# usbcan_20190426.net
KiCad netlist of a schematic drawn in EAGLE
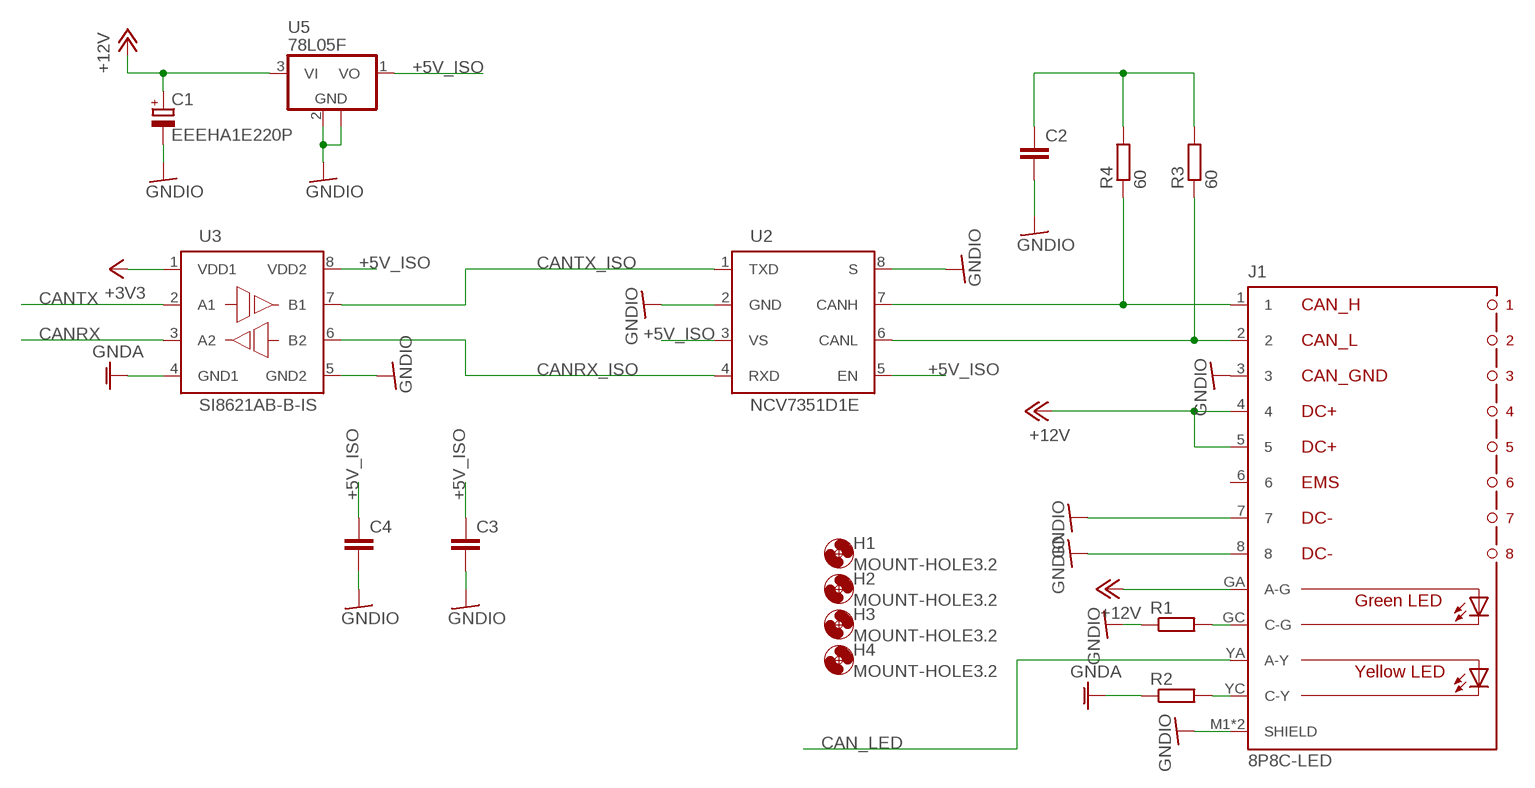
[diagram p0: schematic, sheet 1]
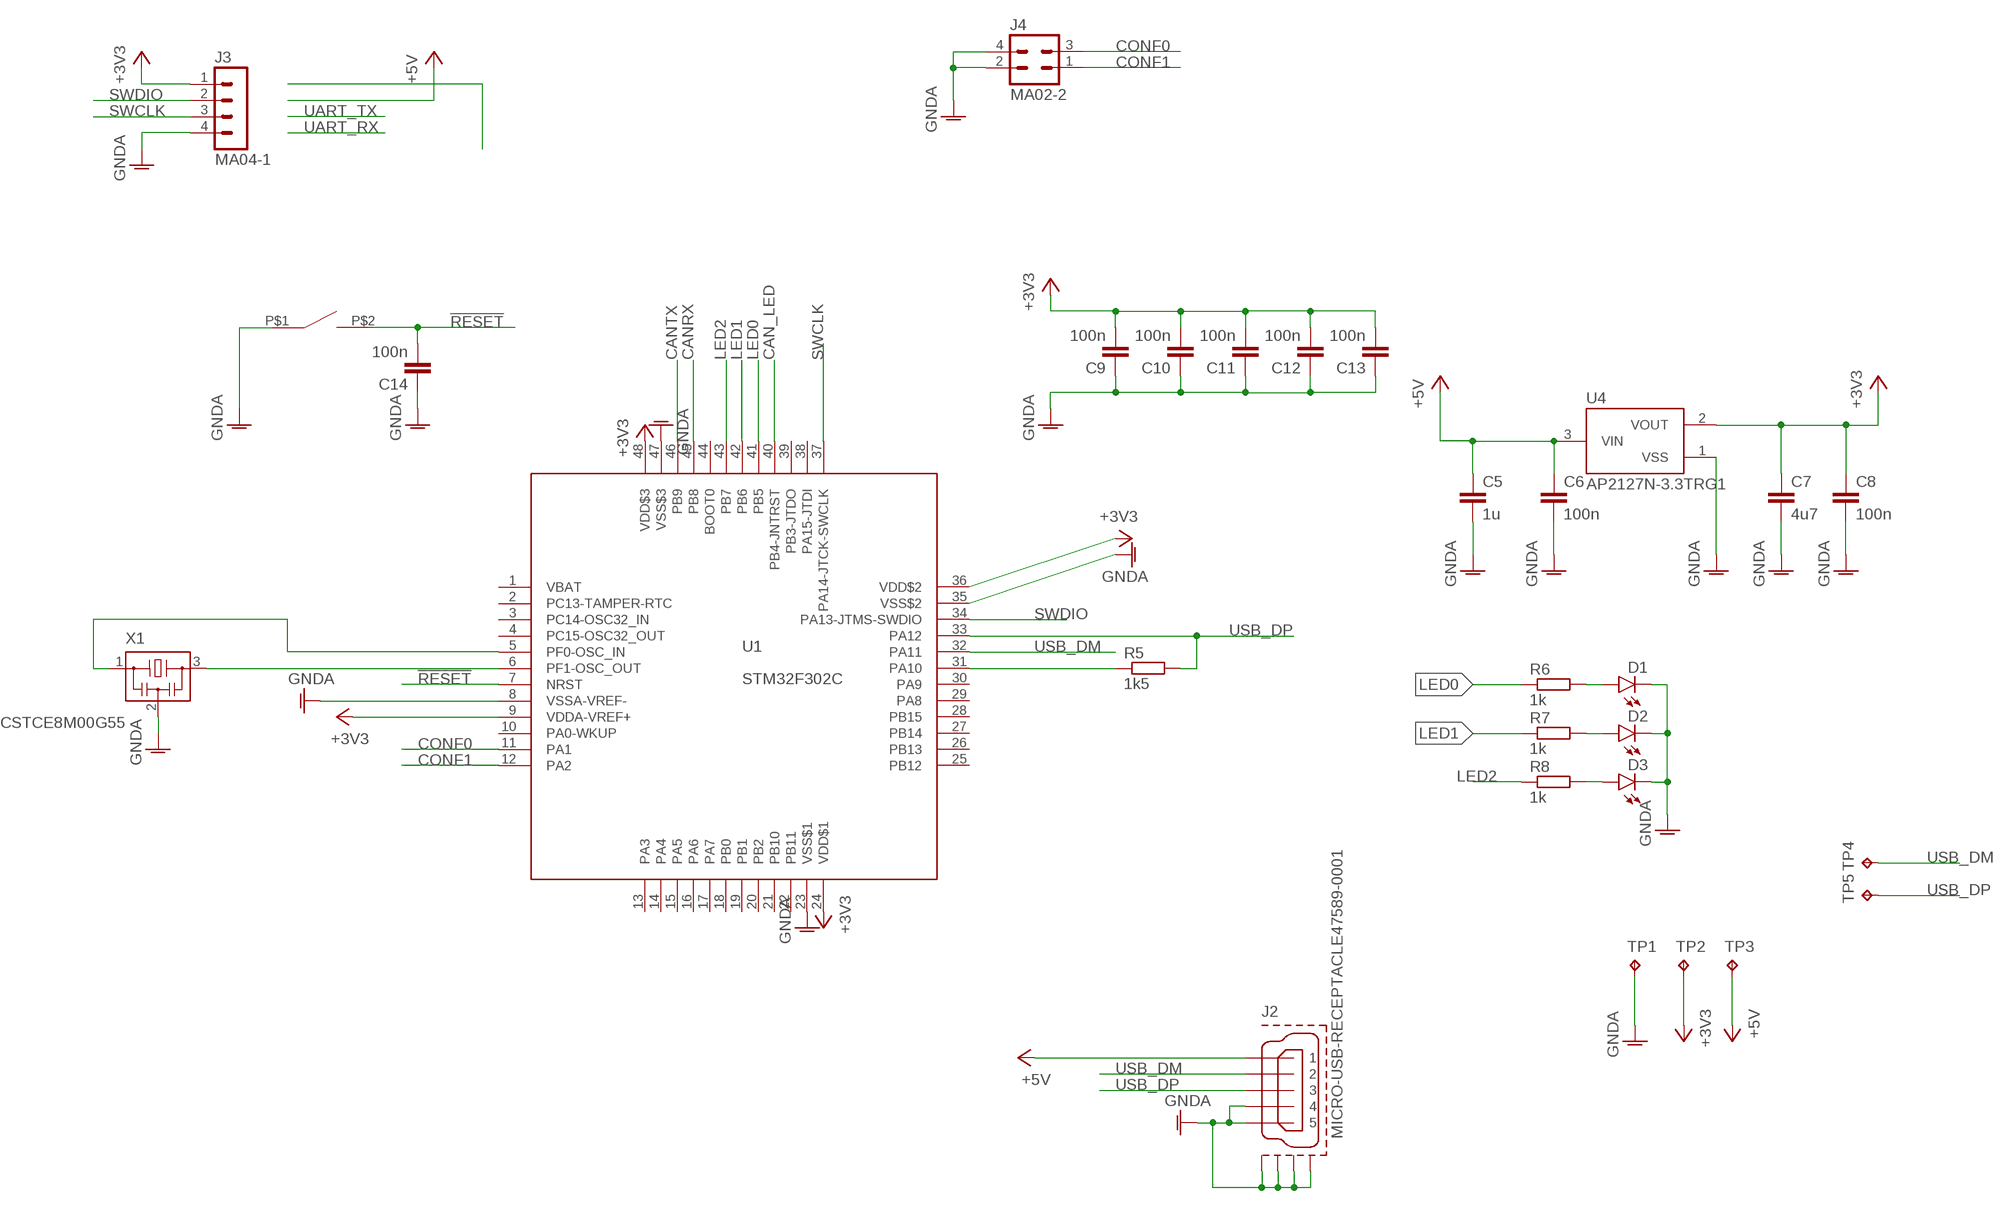
[diagram p1: schematic, sheet 2]

(export (version "E")
  (design (tool "Eeschema 10.0.6"))
  (components
    (comp (ref "C5")
      (value "1u")
      (footprint "eagle-import:C0603")
      (libsource (lib "eagle-import") (part "C-EUC0603"))
    )
    (comp (ref "C6")
      (value "100n")
      (footprint "eagle-import:C0603")
      (libsource (lib "eagle-import") (part "C-EUC0603"))
    )
    (comp (ref "C7")
      (value "4u7")
      (footprint "eagle-import:C0805")
      (libsource (lib "eagle-import") (part "C-EUC0805"))
    )
    (comp (ref "C8")
      (value "100n")
      (footprint "eagle-import:C0603")
      (libsource (lib "eagle-import") (part "C-EUC0603"))
    )
    (comp (ref "C9")
      (value "100n")
      (footprint "eagle-import:C0603")
      (libsource (lib "eagle-import") (part "C-EUC0603"))
    )
    (comp (ref "C10")
      (value "100n")
      (footprint "eagle-import:C0603")
      (libsource (lib "eagle-import") (part "C-EUC0603"))
    )
    (comp (ref "C11")
      (value "100n")
      (footprint "eagle-import:C0603")
      (libsource (lib "eagle-import") (part "C-EUC0603"))
    )
    (comp (ref "C12")
      (value "100n")
      (footprint "eagle-import:C0603")
      (libsource (lib "eagle-import") (part "C-EUC0603"))
    )
    (comp (ref "C13")
      (value "100n")
      (footprint "eagle-import:C0603")
      (libsource (lib "eagle-import") (part "C-EUC0603"))
    )
    (comp (ref "C14")
      (value "100n")
      (footprint "eagle-import:C0603")
      (libsource (lib "eagle-import") (part "C-EUC0603"))
    )
    (comp (ref "D1")
      (value "LEDCHIPLED_0805")
      (footprint "eagle-import:CHIPLED_0805")
      (libsource (lib "eagle-import") (part "LEDCHIPLED_0805"))
    )
    (comp (ref "D2")
      (value "LEDCHIPLED_0805")
      (footprint "eagle-import:CHIPLED_0805")
      (libsource (lib "eagle-import") (part "LEDCHIPLED_0805"))
    )
    (comp (ref "D3")
      (value "LEDCHIPLED_0805")
      (footprint "eagle-import:CHIPLED_0805")
      (libsource (lib "eagle-import") (part "LEDCHIPLED_0805"))
    )
    (comp (ref "J2")
      (value "MICRO-USB-RECEPTACLE47589-0001")
      (footprint "eagle-import:47589-0001")
      (libsource (lib "eagle-import") (part "MICRO-USB-RECEPTACLE47589-0001"))
    )
    (comp (ref "J3")
      (value "MA04-1")
      (footprint "eagle-import:MA04-1")
      (libsource (lib "eagle-import") (part "MA04-1"))
    )
    (comp (ref "J4")
      (value "MA02-2")
      (footprint "eagle-import:MA02-2W")
      (libsource (lib "eagle-import") (part "MA02-2"))
    )
    (comp (ref "R5")
      (value "1k5")
      (footprint "eagle-import:R0603")
      (libsource (lib "eagle-import") (part "R-EU_R0603"))
    )
    (comp (ref "R6")
      (value "1k")
      (footprint "eagle-import:R0603")
      (libsource (lib "eagle-import") (part "R-EU_R0603"))
    )
    (comp (ref "R7")
      (value "1k")
      (footprint "eagle-import:R0603")
      (libsource (lib "eagle-import") (part "R-EU_R0603"))
    )
    (comp (ref "R8")
      (value "1k")
      (footprint "eagle-import:R0603")
      (libsource (lib "eagle-import") (part "R-EU_R0603"))
    )
    (comp (ref "S1")
      (value "SWITCH_TACTILETOP")
      (footprint "eagle-import:SWITCH_TACTILE_3X6")
      (libsource (lib "eagle-import") (part "SWITCH_TACTILETOP"))
    )
    (comp (ref "TP1")
      (value "TPB1,27")
      (footprint "eagle-import:B1,27")
      (libsource (lib "eagle-import") (part "TPB1,27"))
    )
    (comp (ref "TP2")
      (value "TPB1,27")
      (footprint "eagle-import:B1,27")
      (libsource (lib "eagle-import") (part "TPB1,27"))
    )
    (comp (ref "TP3")
      (value "TPB1,27")
      (footprint "eagle-import:B1,27")
      (libsource (lib "eagle-import") (part "TPB1,27"))
    )
    (comp (ref "TP4")
      (value "TPB1,27")
      (footprint "eagle-import:B1,27")
      (libsource (lib "eagle-import") (part "TPB1,27"))
    )
    (comp (ref "TP5")
      (value "TPB1,27")
      (footprint "eagle-import:B1,27")
      (libsource (lib "eagle-import") (part "TPB1,27"))
    )
    (comp (ref "U1")
      (value "STM32F302C")
      (footprint "eagle-import:LQFP48")
      (libsource (lib "eagle-import") (part "STM32F303C"))
    )
    (comp (ref "U4")
      (value "AP2127N-3.3TRG1")
      (footprint "eagle-import:SOT95P240X110-3")
      (libsource (lib "eagle-import") (part "XC6206"))
    )
    (comp (ref "X1")
      (value "CSTCE8M00G55")
      (footprint "eagle-import:CSTCE8M00G55")
      (libsource (lib "eagle-import") (part "CSTCE8M00G55"))
    )
    (comp (ref "C1")
      (value "EEEHA1E220P")
      (footprint "eagle-import:153CLV-0605")
      (libsource (lib "eagle-import") (part "CPOL-EU153CLV-0605"))
    )
    (comp (ref "C2")
      (value "C-EUC0603")
      (footprint "eagle-import:C0603")
      (libsource (lib "eagle-import") (part "rcl_334_C-EUC0603"))
    )
    (comp (ref "C3")
      (value "C-EUC0603")
      (footprint "eagle-import:C0603")
      (libsource (lib "eagle-import") (part "rcl_334_C-EUC0603"))
    )
    (comp (ref "C4")
      (value "C-EUC0603")
      (footprint "eagle-import:C0603")
      (libsource (lib "eagle-import") (part "rcl_334_C-EUC0603"))
    )
    (comp (ref "H1")
      (value "MOUNT-HOLE3.2")
      (footprint "eagle-import:3,2")
      (libsource (lib "eagle-import") (part "MOUNT-HOLE3.2"))
    )
    (comp (ref "H2")
      (value "MOUNT-HOLE3.2")
      (footprint "eagle-import:3,2")
      (libsource (lib "eagle-import") (part "MOUNT-HOLE3.2"))
    )
    (comp (ref "H3")
      (value "MOUNT-HOLE3.2")
      (footprint "eagle-import:3,2")
      (libsource (lib "eagle-import") (part "MOUNT-HOLE3.2"))
    )
    (comp (ref "H4")
      (value "MOUNT-HOLE3.2")
      (footprint "eagle-import:3,2")
      (libsource (lib "eagle-import") (part "MOUNT-HOLE3.2"))
    )
    (comp (ref "J1")
      (value "8P8C-LED")
      (footprint "eagle-import:8P8C-LED")
      (libsource (lib "eagle-import") (part "8P8C-LED"))
    )
    (comp (ref "R1")
      (value "R-EU_R0603")
      (footprint "eagle-import:R0603")
      (libsource (lib "eagle-import") (part "rcl_334_R-EU_R0603"))
    )
    (comp (ref "R2")
      (value "R-EU_R0603")
      (footprint "eagle-import:R0603")
      (libsource (lib "eagle-import") (part "rcl_334_R-EU_R0603"))
    )
    (comp (ref "R3")
      (value "60")
      (footprint "eagle-import:R0603")
      (libsource (lib "eagle-import") (part "rcl_334_R-EU_R0603"))
    )
    (comp (ref "R4")
      (value "60")
      (footprint "eagle-import:R0603")
      (libsource (lib "eagle-import") (part "rcl_334_R-EU_R0603"))
    )
    (comp (ref "U2")
      (value "NCV7351D1E")
      (footprint "eagle-import:SO08")
      (libsource (lib "eagle-import") (part "NCV7351D1E"))
    )
    (comp (ref "U3")
      (value "SI8621AB-B-IS")
      (footprint "eagle-import:SO08")
      (libsource (lib "eagle-import") (part "SI8621AB-B-IS"))
    )
    (comp (ref "U5")
      (value "78L05F")
      (footprint "eagle-import:SOT89")
      (libsource (lib "eagle-import") (part "78LF05"))
    )
  )
  (nets
    (net (code "1") (name "+3V3") (class "Default")
      (node (ref "C10") (pin "2") (pinfunction "2_2") (pintype "passive"))
      (node (ref "C11") (pin "2") (pinfunction "2_2") (pintype "passive"))
      (node (ref "C12") (pin "2") (pinfunction "2_2") (pintype "passive"))
      (node (ref "C13") (pin "2") (pinfunction "2_2") (pintype "passive"))
      (node (ref "C7") (pin "1") (pinfunction "1_1") (pintype "passive"))
      (node (ref "C8") (pin "1") (pinfunction "1_1") (pintype "passive"))
      (node (ref "C9") (pin "2") (pinfunction "2_2") (pintype "passive"))
      (node (ref "J3") (pin "1") (pinfunction "1_1") (pintype "passive"))
      (node (ref "TP2") (pin "TP") (pinfunction "TP_TP") (pintype "input"))
      (node (ref "U1") (pin "24") (pinfunction "VDD$1_24") (pintype "passive"))
      (node (ref "U1") (pin "36") (pinfunction "VDD$2_36") (pintype "passive"))
      (node (ref "U1") (pin "48") (pinfunction "VDD$3_48") (pintype "passive"))
      (node (ref "U1") (pin "9") (pinfunction "VDDA-VREF+_9") (pintype "bidirectional"))
      (node (ref "U3") (pin "1") (pinfunction "VDD1_1") (pintype "power_in"))
      (node (ref "U4") (pin "2") (pinfunction "VOUT_2") (pintype "bidirectional"))
    )
    (net (code "2") (name "+5V") (class "Default")
      (node (ref "C5") (pin "1") (pinfunction "1_1") (pintype "passive"))
      (node (ref "C6") (pin "1") (pinfunction "1_1") (pintype "passive"))
      (node (ref "J2") (pin "1") (pinfunction "1_1") (pintype "input"))
      (node (ref "TP3") (pin "TP") (pinfunction "TP_TP") (pintype "input"))
      (node (ref "U4") (pin "3") (pinfunction "VIN_3") (pintype "bidirectional"))
    )
    (net (code "3") (name "+5V_ISO") (class "Default")
      (node (ref "C3") (pin "1") (pinfunction "1_1") (pintype "passive"))
      (node (ref "C4") (pin "1") (pinfunction "1_1") (pintype "passive"))
      (node (ref "U2") (pin "3") (pinfunction "VS_3") (pintype "power_in"))
      (node (ref "U2") (pin "5") (pinfunction "EN_5") (pintype "input"))
      (node (ref "U3") (pin "8") (pinfunction "VDD2_8") (pintype "power_in"))
      (node (ref "U5") (pin "1") (pinfunction "VO_1") (pintype "passive"))
    )
    (net (code "4") (name "+12V") (class "Default")
      (node (ref "C1") (pin "+") (pinfunction "+_+") (pintype "passive"))
      (node (ref "J1") (pin "4") (pinfunction "4_4") (pintype "input"))
      (node (ref "J1") (pin "5") (pinfunction "5_5") (pintype "input"))
      (node (ref "J1") (pin "GA") (pinfunction "A-G_GA") (pintype "passive"))
      (node (ref "U5") (pin "3") (pinfunction "VI_3") (pintype "input"))
    )
    (net (code "5") (name "CANRX") (class "Default")
      (node (ref "U1") (pin "45") (pinfunction "PB8_45") (pintype "bidirectional"))
      (node (ref "U3") (pin "3") (pinfunction "A2_3") (pintype "output"))
    )
    (net (code "6") (name "CANRX_ISO") (class "Default")
      (node (ref "U2") (pin "4") (pinfunction "RXD_4") (pintype "output"))
      (node (ref "U3") (pin "6") (pinfunction "B2_6") (pintype "output"))
    )
    (net (code "7") (name "CANTX") (class "Default")
      (node (ref "U1") (pin "46") (pinfunction "PB9_46") (pintype "bidirectional"))
      (node (ref "U3") (pin "2") (pinfunction "A1_2") (pintype "input"))
    )
    (net (code "8") (name "CANTX_ISO") (class "Default")
      (node (ref "U2") (pin "1") (pinfunction "TXD_1") (pintype "input"))
      (node (ref "U3") (pin "7") (pinfunction "B1_7") (pintype "output"))
    )
    (net (code "9") (name "CAN_LED") (class "Default")
      (node (ref "J1") (pin "YA") (pinfunction "A-Y_YA") (pintype "passive"))
      (node (ref "U1") (pin "40") (pinfunction "PB4-JNTRST_40") (pintype "bidirectional"))
    )
    (net (code "10") (name "CONF0") (class "Default")
      (node (ref "J4") (pin "3") (pinfunction "3_3") (pintype "passive"))
      (node (ref "U1") (pin "11") (pinfunction "PA1_11") (pintype "bidirectional"))
    )
    (net (code "11") (name "CONF1") (class "Default")
      (node (ref "J4") (pin "1") (pinfunction "1_1") (pintype "passive"))
      (node (ref "U1") (pin "12") (pinfunction "PA2_12") (pintype "bidirectional"))
    )
    (net (code "12") (name "GNDA") (class "Default")
      (node (ref "C10") (pin "1") (pinfunction "1_1") (pintype "passive"))
      (node (ref "C11") (pin "1") (pinfunction "1_1") (pintype "passive"))
      (node (ref "C12") (pin "1") (pinfunction "1_1") (pintype "passive"))
      (node (ref "C13") (pin "1") (pinfunction "1_1") (pintype "passive"))
      (node (ref "C14") (pin "1") (pinfunction "1_1") (pintype "passive"))
      (node (ref "C5") (pin "2") (pinfunction "2_2") (pintype "passive"))
      (node (ref "C6") (pin "2") (pinfunction "2_2") (pintype "passive"))
      (node (ref "C7") (pin "2") (pinfunction "2_2") (pintype "passive"))
      (node (ref "C8") (pin "2") (pinfunction "2_2") (pintype "passive"))
      (node (ref "C9") (pin "1") (pinfunction "1_1") (pintype "passive"))
      (node (ref "D1") (pin "C") (pinfunction "C_C") (pintype "passive"))
      (node (ref "D2") (pin "C") (pinfunction "C_C") (pintype "passive"))
      (node (ref "D3") (pin "C") (pinfunction "C_C") (pintype "passive"))
      (node (ref "J2") (pin "4") (pinfunction "4_4") (pintype "input"))
      (node (ref "J2") (pin "5") (pinfunction "5_5") (pintype "input"))
      (node (ref "J2") (pin "CASING1") (pinfunction "GND1_CASING1") (pintype "bidirectional"))
      (node (ref "J2") (pin "CASING2") (pinfunction "GND2_CASING2") (pintype "bidirectional"))
      (node (ref "J2") (pin "CASING3") (pinfunction "GND3_CASING3") (pintype "bidirectional"))
      (node (ref "J2") (pin "CASING4") (pinfunction "GND4_CASING4") (pintype "bidirectional"))
      (node (ref "J2") (pin "P$1") (pinfunction "GND1_P$1") (pintype "bidirectional"))
      (node (ref "J2") (pin "P$2") (pinfunction "GND1_P$2") (pintype "bidirectional"))
      (node (ref "J2") (pin "P$3") (pinfunction "GND2_P$3") (pintype "bidirectional"))
      (node (ref "J2") (pin "P$4") (pinfunction "GND2_P$4") (pintype "bidirectional"))
      (node (ref "J3") (pin "4") (pinfunction "4_4") (pintype "passive"))
      (node (ref "J4") (pin "2") (pinfunction "2_2") (pintype "passive"))
      (node (ref "J4") (pin "4") (pinfunction "4_4") (pintype "passive"))
      (node (ref "R2") (pin "1") (pinfunction "1_1") (pintype "passive"))
      (node (ref "S1") (pin "P$1") (pinfunction "1_P$1") (pintype "bidirectional"))
      (node (ref "TP1") (pin "TP") (pinfunction "TP_TP") (pintype "input"))
      (node (ref "U1") (pin "23") (pinfunction "VSS$1_23") (pintype "passive"))
      (node (ref "U1") (pin "35") (pinfunction "VSS$2_35") (pintype "passive"))
      (node (ref "U1") (pin "47") (pinfunction "VSS$3_47") (pintype "passive"))
      (node (ref "U1") (pin "8") (pinfunction "VSSA-VREF-_8") (pintype "bidirectional"))
      (node (ref "U3") (pin "4") (pinfunction "GND1_4") (pintype "power_in"))
      (node (ref "U4") (pin "1") (pinfunction "VSS_1") (pintype "bidirectional"))
      (node (ref "X1") (pin "2") (pinfunction "2_2") (pintype "passive"))
    )
    (net (code "13") (name "GNDIO") (class "Default")
      (node (ref "C1") (pin "-") (pinfunction "-_-") (pintype "passive"))
      (node (ref "C2") (pin "2") (pinfunction "2_2") (pintype "passive"))
      (node (ref "C3") (pin "2") (pinfunction "2_2") (pintype "passive"))
      (node (ref "C4") (pin "2") (pinfunction "2_2") (pintype "passive"))
      (node (ref "J1") (pin "3") (pinfunction "3_3") (pintype "input"))
      (node (ref "J1") (pin "7") (pinfunction "7_7") (pintype "input"))
      (node (ref "J1") (pin "8") (pinfunction "8_8") (pintype "input"))
      (node (ref "J1") (pin "M1") (pinfunction "SHIELD_M1") (pintype "passive"))
      (node (ref "J1") (pin "M2") (pinfunction "SHIELD_M2") (pintype "passive"))
      (node (ref "R1") (pin "1") (pinfunction "1_1") (pintype "passive"))
      (node (ref "U2") (pin "2") (pinfunction "GND_2") (pintype "power_in"))
      (node (ref "U2") (pin "8") (pinfunction "S_8") (pintype "input"))
      (node (ref "U3") (pin "5") (pinfunction "GND2_5") (pintype "power_in"))
      (node (ref "U5") (pin "2") (pinfunction "GND_2") (pintype "passive"))
      (node (ref "U5") (pin "2@1") (pinfunction "GND_2@1") (pintype "passive"))
    )
    (net (code "14") (name "LED0") (class "Default")
      (node (ref "R6") (pin "1") (pinfunction "1_1") (pintype "passive"))
      (node (ref "U1") (pin "41") (pinfunction "PB5_41") (pintype "bidirectional"))
    )
    (net (code "15") (name "LED1") (class "Default")
      (node (ref "R7") (pin "1") (pinfunction "1_1") (pintype "passive"))
      (node (ref "U1") (pin "42") (pinfunction "PB6_42") (pintype "bidirectional"))
    )
    (net (code "16") (name "LED2") (class "Default")
      (node (ref "R8") (pin "1") (pinfunction "1_1") (pintype "passive"))
      (node (ref "U1") (pin "43") (pinfunction "PB7_43") (pintype "bidirectional"))
    )
    (net (code "17") (name "Net-(C2-Pad1)") (class "Default")
      (node (ref "C2") (pin "1") (pinfunction "1_1") (pintype "passive"))
      (node (ref "R3") (pin "2") (pinfunction "2_2") (pintype "passive"))
      (node (ref "R4") (pin "2") (pinfunction "2_2") (pintype "passive"))
    )
    (net (code "18") (name "Net-(D1-PadA)") (class "Default")
      (node (ref "D1") (pin "A") (pinfunction "A_A") (pintype "passive"))
      (node (ref "R6") (pin "2") (pinfunction "2_2") (pintype "passive"))
    )
    (net (code "19") (name "Net-(D2-PadA)") (class "Default")
      (node (ref "D2") (pin "A") (pinfunction "A_A") (pintype "passive"))
      (node (ref "R7") (pin "2") (pinfunction "2_2") (pintype "passive"))
    )
    (net (code "20") (name "Net-(D3-PadA)") (class "Default")
      (node (ref "D3") (pin "A") (pinfunction "A_A") (pintype "passive"))
      (node (ref "R8") (pin "2") (pinfunction "2_2") (pintype "passive"))
    )
    (net (code "21") (name "Net-(J1-C-G)") (class "Default")
      (node (ref "J1") (pin "GC") (pinfunction "C-G_GC") (pintype "passive"))
      (node (ref "R1") (pin "2") (pinfunction "2_2") (pintype "passive"))
    )
    (net (code "22") (name "Net-(J1-C-Y)") (class "Default")
      (node (ref "J1") (pin "YC") (pinfunction "C-Y_YC") (pintype "passive"))
      (node (ref "R2") (pin "2") (pinfunction "2_2") (pintype "passive"))
    )
    (net (code "23") (name "Net-(U1-PA10)") (class "Default")
      (node (ref "R5") (pin "1") (pinfunction "1_1") (pintype "passive"))
      (node (ref "U1") (pin "31") (pinfunction "PA10_31") (pintype "bidirectional"))
    )
    (net (code "24") (name "Net-(U1-PF0-OSC_IN)") (class "Default")
      (node (ref "U1") (pin "5") (pinfunction "PF0-OSC_IN_5") (pintype "input"))
      (node (ref "X1") (pin "1") (pinfunction "1_1") (pintype "passive"))
    )
    (net (code "25") (name "Net-(U1-PF1-OSC_OUT)") (class "Default")
      (node (ref "U1") (pin "6") (pinfunction "PF1-OSC_OUT_6") (pintype "output"))
      (node (ref "X1") (pin "3") (pinfunction "3_3") (pintype "passive"))
    )
    (net (code "26") (name "Net-(U2-CANH)") (class "Default")
      (node (ref "J1") (pin "1") (pinfunction "1_1") (pintype "input"))
      (node (ref "R4") (pin "1") (pinfunction "1_1") (pintype "passive"))
      (node (ref "U2") (pin "7") (pinfunction "CANH_7") (pintype "output"))
    )
    (net (code "27") (name "Net-(U2-CANL)") (class "Default")
      (node (ref "J1") (pin "2") (pinfunction "2_2") (pintype "input"))
      (node (ref "R3") (pin "1") (pinfunction "1_1") (pintype "passive"))
      (node (ref "U2") (pin "6") (pinfunction "CANL_6") (pintype "output"))
    )
    (net (code "28") (name "SWCLK") (class "Default")
      (node (ref "J3") (pin "3") (pinfunction "3_3") (pintype "passive"))
      (node (ref "U1") (pin "37") (pinfunction "PA14-JTCK-SWCLK_37") (pintype "bidirectional"))
    )
    (net (code "29") (name "SWDIO") (class "Default")
      (node (ref "J3") (pin "2") (pinfunction "2_2") (pintype "passive"))
      (node (ref "U1") (pin "34") (pinfunction "PA13-JTMS-SWDIO_34") (pintype "bidirectional"))
    )
    (net (code "32") (name "USB_DM") (class "Default")
      (node (ref "J2") (pin "2") (pinfunction "2_2") (pintype "input"))
      (node (ref "TP4") (pin "TP") (pinfunction "TP_TP") (pintype "input"))
      (node (ref "U1") (pin "32") (pinfunction "PA11_32") (pintype "bidirectional"))
    )
    (net (code "33") (name "USB_DP") (class "Default")
      (node (ref "J2") (pin "3") (pinfunction "3_3") (pintype "input"))
      (node (ref "R5") (pin "2") (pinfunction "2_2") (pintype "passive"))
      (node (ref "TP5") (pin "TP") (pinfunction "TP_TP") (pintype "input"))
      (node (ref "U1") (pin "33") (pinfunction "PA12_33") (pintype "bidirectional"))
    )
    (net (code "34") (name "unconnected-(J1-Pad6)") (class "Default")
      (node (ref "J1") (pin "6") (pinfunction "6_6") (pintype "input"))
    )
    (net (code "35") (name "unconnected-(U1-BOOT0-Pad44)") (class "Default")
      (node (ref "U1") (pin "44") (pinfunction "BOOT0_44") (pintype "input"))
    )
    (net (code "36") (name "unconnected-(U1-PA0-WKUP-Pad10)") (class "Default")
      (node (ref "U1") (pin "10") (pinfunction "PA0-WKUP_10") (pintype "bidirectional"))
    )
    (net (code "37") (name "unconnected-(U1-PA3-Pad13)") (class "Default")
      (node (ref "U1") (pin "13") (pinfunction "PA3_13") (pintype "bidirectional"))
    )
    (net (code "38") (name "unconnected-(U1-PA4-Pad14)") (class "Default")
      (node (ref "U1") (pin "14") (pinfunction "PA4_14") (pintype "bidirectional"))
    )
    (net (code "39") (name "unconnected-(U1-PA5-Pad15)") (class "Default")
      (node (ref "U1") (pin "15") (pinfunction "PA5_15") (pintype "bidirectional"))
    )
    (net (code "40") (name "unconnected-(U1-PA6-Pad16)") (class "Default")
      (node (ref "U1") (pin "16") (pinfunction "PA6_16") (pintype "bidirectional"))
    )
    (net (code "41") (name "unconnected-(U1-PA7-Pad17)") (class "Default")
      (node (ref "U1") (pin "17") (pinfunction "PA7_17") (pintype "bidirectional"))
    )
    (net (code "42") (name "unconnected-(U1-PA8-Pad29)") (class "Default")
      (node (ref "U1") (pin "29") (pinfunction "PA8_29") (pintype "bidirectional"))
    )
    (net (code "43") (name "unconnected-(U1-PA9-Pad30)") (class "Default")
      (node (ref "U1") (pin "30") (pinfunction "PA9_30") (pintype "bidirectional"))
    )
    (net (code "44") (name "unconnected-(U1-PA15-JTDI-Pad38)") (class "Default")
      (node (ref "U1") (pin "38") (pinfunction "PA15-JTDI_38") (pintype "bidirectional"))
    )
    (net (code "45") (name "unconnected-(U1-PB0-Pad18)") (class "Default")
      (node (ref "U1") (pin "18") (pinfunction "PB0_18") (pintype "bidirectional"))
    )
    (net (code "46") (name "unconnected-(U1-PB1-Pad19)") (class "Default")
      (node (ref "U1") (pin "19") (pinfunction "PB1_19") (pintype "bidirectional"))
    )
    (net (code "47") (name "unconnected-(U1-PB2-Pad20)") (class "Default")
      (node (ref "U1") (pin "20") (pinfunction "PB2_20") (pintype "bidirectional"))
    )
    (net (code "48") (name "unconnected-(U1-PB3-JTDO-Pad39)") (class "Default")
      (node (ref "U1") (pin "39") (pinfunction "PB3-JTDO_39") (pintype "bidirectional"))
    )
    (net (code "49") (name "unconnected-(U1-PB10-Pad21)") (class "Default")
      (node (ref "U1") (pin "21") (pinfunction "PB10_21") (pintype "bidirectional"))
    )
    (net (code "50") (name "unconnected-(U1-PB11-Pad22)") (class "Default")
      (node (ref "U1") (pin "22") (pinfunction "PB11_22") (pintype "bidirectional"))
    )
    (net (code "51") (name "unconnected-(U1-PB12-Pad25)") (class "Default")
      (node (ref "U1") (pin "25") (pinfunction "PB12_25") (pintype "bidirectional"))
    )
    (net (code "52") (name "unconnected-(U1-PB13-Pad26)") (class "Default")
      (node (ref "U1") (pin "26") (pinfunction "PB13_26") (pintype "bidirectional"))
    )
    (net (code "53") (name "unconnected-(U1-PB14-Pad27)") (class "Default")
      (node (ref "U1") (pin "27") (pinfunction "PB14_27") (pintype "bidirectional"))
    )
    (net (code "54") (name "unconnected-(U1-PB15-Pad28)") (class "Default")
      (node (ref "U1") (pin "28") (pinfunction "PB15_28") (pintype "bidirectional"))
    )
    (net (code "55") (name "unconnected-(U1-PC13-TAMPER-RTC-Pad2)") (class "Default")
      (node (ref "U1") (pin "2") (pinfunction "PC13-TAMPER-RTC_2") (pintype "bidirectional"))
    )
    (net (code "56") (name "unconnected-(U1-PC14-OSC32_IN-Pad3)") (class "Default")
      (node (ref "U1") (pin "3") (pinfunction "PC14-OSC32_IN_3") (pintype "bidirectional"))
    )
    (net (code "57") (name "unconnected-(U1-PC15-OSC32_OUT-Pad4)") (class "Default")
      (node (ref "U1") (pin "4") (pinfunction "PC15-OSC32_OUT_4") (pintype "bidirectional"))
    )
    (net (code "58") (name "unconnected-(U1-VBAT-Pad1)") (class "Default")
      (node (ref "U1") (pin "1") (pinfunction "VBAT_1") (pintype "passive"))
    )
    (net (code "59") (name "~{RESET}") (class "Default")
      (node (ref "C14") (pin "2") (pinfunction "2_2") (pintype "passive"))
      (node (ref "S1") (pin "P$2") (pinfunction "2_P$2") (pintype "bidirectional"))
      (node (ref "U1") (pin "7") (pinfunction "NRST_7") (pintype "bidirectional"))
    )
  )
)
